# PMT_simulator.net
KiCad netlist of a schematic drawn in Altium Designer
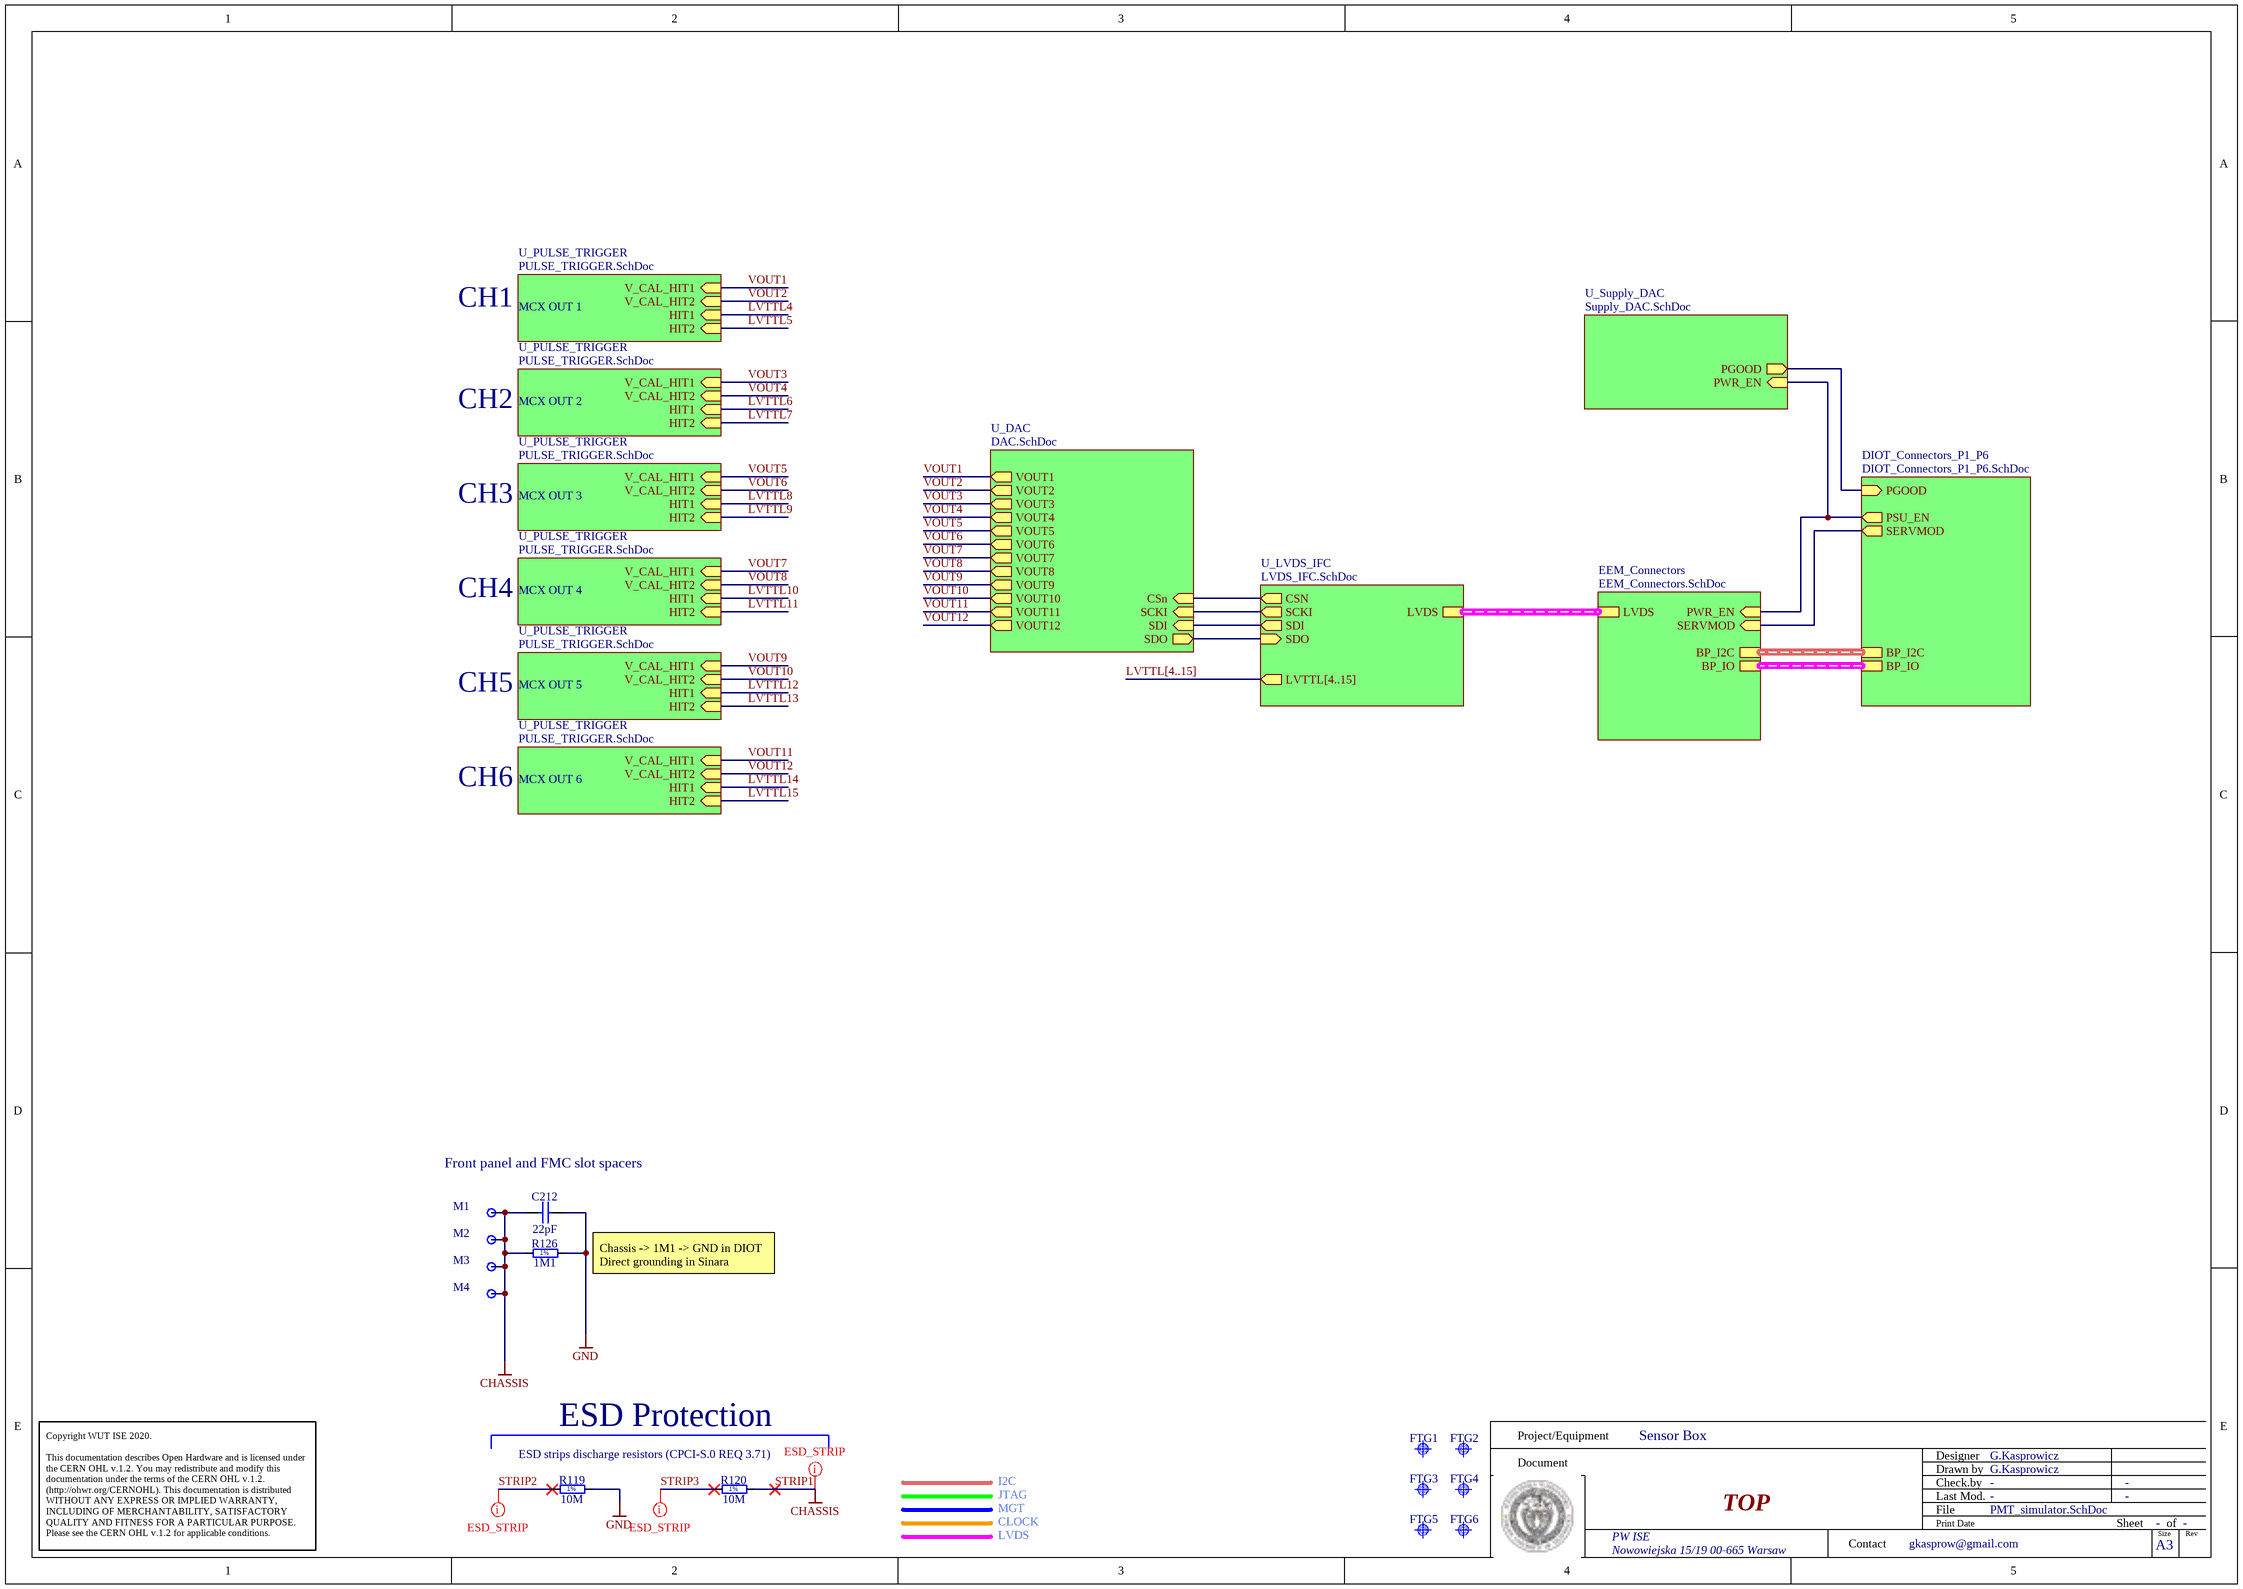
[diagram p0: PMT_simulator.SchDoc]

(export (version "E")
  (design (tool "Eeschema 10.0.6"))
  (components
    (comp (ref "C212")
      (value "22pF")
      (footprint "CAPC1005X55N")
      (description "Non-polarised capacitor")
      (fields
        (field (name "PART NUMBER") "CC0402_22PF_50V_5%_C0G")
        (field (name "VOLTAGE") "50V")
        (field (name "AUTHOR") "CERN DEM JLC")
      )
      (libsource (lib "Capacitors") (part "Capacitor - non polarized"))
    )
    (comp (ref "FTG1")
      (value "Use only in PCB")
      (footprint "FIDUCIAL_TOP_S100-200")
      (description "Fiducial Target")
      (fields (field (name "PART NUMBER") "FIDUCIAL_TARGET_S100-200") (field (name "AUTHOR") "CERN DEM JLC"))
      (libsource (lib "Eletro-mechanical") (part "Fiducial Target"))
    )
    (comp (ref "FTG2")
      (value "Use only in PCB")
      (footprint "FIDUCIAL_TOP_S100-200")
      (description "Fiducial Target")
      (fields (field (name "PART NUMBER") "FIDUCIAL_TARGET_S100-200") (field (name "AUTHOR") "CERN DEM JLC"))
      (libsource (lib "Eletro-mechanical") (part "Fiducial Target"))
    )
    (comp (ref "FTG3")
      (value "Use only in PCB")
      (footprint "FIDUCIAL_TOP_S100-200")
      (description "Fiducial Target")
      (fields (field (name "PART NUMBER") "FIDUCIAL_TARGET_S100-200") (field (name "AUTHOR") "CERN DEM JLC"))
      (libsource (lib "Eletro-mechanical") (part "Fiducial Target"))
    )
    (comp (ref "FTG4")
      (value "Use only in PCB")
      (footprint "FIDUCIAL_TOP_S100-200")
      (description "Fiducial Target")
      (fields (field (name "PART NUMBER") "FIDUCIAL_TARGET_S100-200") (field (name "AUTHOR") "CERN DEM JLC"))
      (libsource (lib "Eletro-mechanical") (part "Fiducial Target"))
    )
    (comp (ref "FTG5")
      (value "Use only in PCB")
      (footprint "FIDUCIAL_TOP_S100-200")
      (description "Fiducial Target")
      (fields (field (name "PART NUMBER") "FIDUCIAL_TARGET_S100-200") (field (name "AUTHOR") "CERN DEM JLC"))
      (libsource (lib "Eletro-mechanical") (part "Fiducial Target"))
    )
    (comp (ref "FTG6")
      (value "Use only in PCB")
      (footprint "FIDUCIAL_TOP_S100-200")
      (description "Fiducial Target")
      (fields (field (name "PART NUMBER") "FIDUCIAL_TARGET_S100-200") (field (name "AUTHOR") "CERN DEM JLC"))
      (libsource (lib "Eletro-mechanical") (part "Fiducial Target"))
    )
    (comp (ref "M1")
      (value "Plated Hole")
      (footprint "MTG300_600")
      (description "Single Terminal Socket")
      (fields (field (name "PART NUMBER") "PLATED_HOLE3.0_PAD6.0") (field (name "AUTHOR") "CERN DEM JLC"))
      (libsource (lib "Eletro-mechanical") (part "Single Terminal Socket"))
    )
    (comp (ref "M2")
      (value "Plated Hole")
      (footprint "MTG300_600")
      (description "Single Terminal Socket")
      (fields (field (name "PART NUMBER") "PLATED_HOLE3.0_PAD6.0") (field (name "AUTHOR") "CERN DEM JLC"))
      (libsource (lib "Eletro-mechanical") (part "Single Terminal Socket"))
    )
    (comp (ref "M3")
      (value "Plated Hole")
      (footprint "MTG300_600")
      (description "Single Terminal Socket")
      (fields (field (name "PART NUMBER") "PLATED_HOLE3.0_PAD6.0") (field (name "AUTHOR") "CERN DEM JLC"))
      (libsource (lib "Eletro-mechanical") (part "Single Terminal Socket"))
    )
    (comp (ref "M4")
      (value "Plated Hole")
      (footprint "MTG300_600")
      (description "Single Terminal Socket")
      (fields (field (name "PART NUMBER") "PLATED_HOLE3.0_PAD6.0") (field (name "AUTHOR") "CERN DEM JLC"))
      (libsource (lib "Eletro-mechanical") (part "Single Terminal Socket"))
    )
    (comp (ref "R119")
      (value "10M")
      (footprint "RESC2113X55N")
      (description "Resistor - 1%")
      (fields
        (field (name "PART NUMBER") "R0805_10M_1%_0.125W_100PPM_VISHAY_CRCW e3")
        (field (name "POWER") "0.125W")
        (field (name "AUTHOR") "CERN DEM BC")
      )
      (libsource (lib "Resistors") (part "Resistor - 1%"))
    )
    (comp (ref "R120")
      (value "10M")
      (footprint "RESC2113X55N")
      (description "Resistor - 1%")
      (fields
        (field (name "PART NUMBER") "R0805_10M_1%_0.125W_100PPM_VISHAY_CRCW e3")
        (field (name "POWER") "0.125W")
        (field (name "AUTHOR") "CERN DEM BC")
      )
      (libsource (lib "Resistors") (part "Resistor - 1%"))
    )
    (comp (ref "R126")
      (value "1M1")
      (footprint "RESC2012X60N")
      (description "Resistor - 1%")
      (fields
        (field (name "PART NUMBER") "R0805_1M1_1%_0.125W_100PPM")
        (field (name "POWER") "0.125W")
        (field (name "AUTHOR") "CERN DEM JLC")
      )
      (libsource (lib "Resistors") (part "Resistor - 1%"))
    )
  )
  (nets
    (net (code "25") (name "/STRIP2") (class "Default")
      (node (ref "R119") (pin "1") (pinfunction "1_1") (pintype "passive+no_connect"))
    )
    (net (code "26") (name "/STRIP3") (class "Default")
      (node (ref "R120") (pin "1") (pinfunction "1_1") (pintype "passive+no_connect"))
    )
    (net (code "39") (name "CHASSIS") (class "Default")
      (node (ref "C212") (pin "1") (pinfunction "1_1") (pintype "passive"))
      (node (ref "M1") (pin "1") (pinfunction "1_1") (pintype "bidirectional"))
      (node (ref "M2") (pin "1") (pinfunction "1_1") (pintype "bidirectional"))
      (node (ref "M3") (pin "1") (pinfunction "1_1") (pintype "bidirectional"))
      (node (ref "M4") (pin "1") (pinfunction "1_1") (pintype "bidirectional"))
      (node (ref "R120") (pin "2") (pinfunction "2_2") (pintype "passive"))
      (node (ref "R126") (pin "1") (pinfunction "1_1") (pintype "passive"))
    )
    (net (code "40") (name "GND") (class "Default")
      (node (ref "C212") (pin "2") (pinfunction "2_2") (pintype "passive"))
      (node (ref "R119") (pin "2") (pinfunction "2_2") (pintype "passive"))
      (node (ref "R126") (pin "2") (pinfunction "2_2") (pintype "passive"))
    )
  )
)
